# ExternalDisplay.net
KiCad netlist of a schematic drawn in Altium Designer
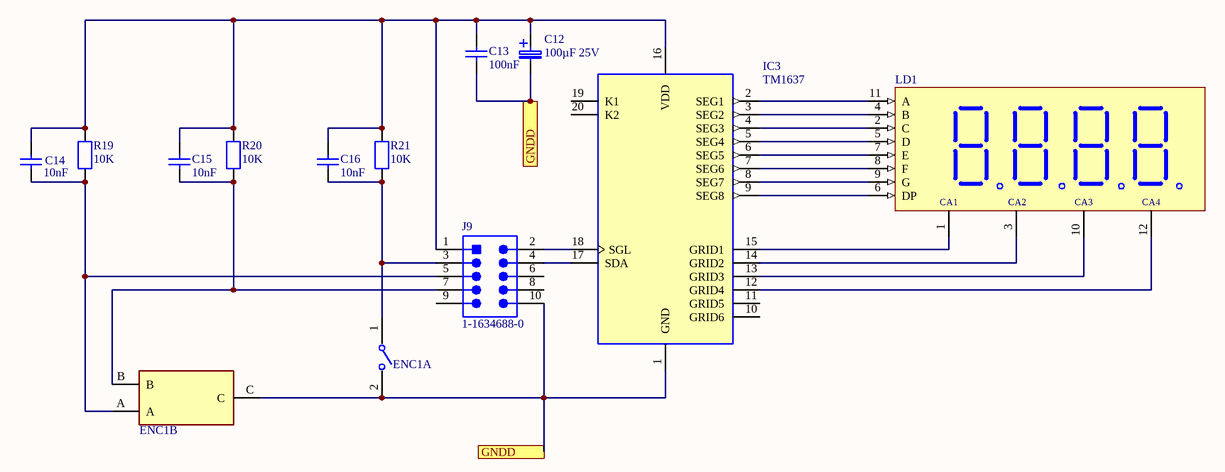
[diagram p0: ExternalDisplay.SchDoc]

(export (version "E")
  (design (tool "Eeschema 10.0.6"))
  (components
    (comp (ref "C12")
      (value "100µF 25V")
      (footprint "TAP106M050BRW")
      (description "Tantalum Capacitors - Solid Leaded 50V 10uF 20% ESR=1.6 Ohm TAP106M050BRW")
      (fields
        (field (name "MOUSER PART NUMBER") "581-TAP106M050BRW")
        (field (name "MANUFACTURER_PART_NUMBER") "TAP106M050BRW")
      )
      (libsource (lib "SolderStation") (part "capacitor THT radial tantalum"))
    )
    (comp (ref "C13")
      (value "100nF")
      (footprint "CAPC2012X88N")
      (fields (field (name "MANUFACTURER") "Kemet") (field (name "PART NUMBER") "C0402C104K4RACTU"))
      (libsource (lib "SolderStation") (part "Capacitor ceramic 0805"))
    )
    (comp (ref "C14")
      (value "10nF")
      (footprint "CAPC2012X88N")
      (fields (field (name "MANUFACTURER") "Kemet") (field (name "PART NUMBER") "C0402C104K4RACTU"))
      (libsource (lib "SolderStation") (part "Capacitor ceramic 0805"))
    )
    (comp (ref "C15")
      (value "10nF")
      (footprint "CAPC2012X88N")
      (fields (field (name "MANUFACTURER") "Kemet") (field (name "PART NUMBER") "C0402C104K4RACTU"))
      (libsource (lib "SolderStation") (part "Capacitor ceramic 0805"))
    )
    (comp (ref "C16")
      (value "10nF")
      (footprint "CAPC2012X88N")
      (fields (field (name "MANUFACTURER") "Kemet") (field (name "PART NUMBER") "C0402C104K4RACTU"))
      (libsource (lib "SolderStation") (part "Capacitor ceramic 0805"))
    )
    (comp (ref "ENC1")
      (value "PEC11R-4220F-S0012")
      (footprint "PEC11R_4220F_S0012")
      (description "ROTARY ENCODER MECHANICAL 12PPR")
      (libsource (lib "") (part "PEC11R-4220F-S0012_1"))
    )
    (comp (ref "IC3")
      (value "TM1637")
      (footprint "N-20")
      (description "LED Drive Control Special Circuit")
      (fields (field (name "MF") "Titan Micro Electronics"))
      (libsource (lib "SolderStation") (part "TM1637"))
    )
    (comp (ref "J9")
      (value "1-1634688-0")
      (footprint "TECO-1-1634688-0-10_V")
      (fields (field (name "MANUFACTURER") "TE Connectivity"))
      (libsource (lib "SolderStation") (part "pin header 2X5 10pins"))
    )
    (comp (ref "LD1")
      (value "KW4-801AVB")
      (footprint "KW4-801AVB/KW4-801CVB")
      (description "4-Digit LED Display TME")
      (libsource (lib "SolderStation") (part "KW4-801AVB"))
    )
    (comp (ref "R19")
      (value "10K")
      (footprint "RESC2012X50N")
      (fields (field (name "MANUFACTURER") "Vishay Dale") (field (name "PART NUMBER") "CRCW08050000Z0EA"))
      (libsource (lib "SolderStation") (part "resistor 0805"))
    )
    (comp (ref "R20")
      (value "10K")
      (footprint "RESC2012X50N")
      (fields (field (name "MANUFACTURER") "Vishay Dale") (field (name "PART NUMBER") "CRCW08050000Z0EA"))
      (libsource (lib "SolderStation") (part "resistor 0805"))
    )
    (comp (ref "R21")
      (value "10K")
      (footprint "RESC2012X50N")
      (fields (field (name "MANUFACTURER") "Vishay Dale") (field (name "PART NUMBER") "CRCW08050000Z0EA"))
      (libsource (lib "SolderStation") (part "resistor 0805"))
    )
  )
  (nets
    (net (code "1") (name "/GNDD") (class "Default")
      (node (ref "C12") (pin "2") (pinfunction "2_2") (pintype "passive"))
      (node (ref "C13") (pin "1") (pinfunction "1_1") (pintype "passive"))
      (node (ref "ENC1") (pin "2") (pinfunction "2_2") (pintype "passive"))
      (node (ref "ENC1") (pin "C") (pinfunction "C_C") (pintype "passive"))
      (node (ref "IC3") (pin "1") (pinfunction "GND_1") (pintype "power_in"))
      (node (ref "J9") (pin "10") (pinfunction "10_10") (pintype "passive"))
    )
    (net (code "2") (name "Net-(C14-Pad1)") (class "Default")
      (node (ref "C14") (pin "1") (pinfunction "1_1") (pintype "passive"))
      (node (ref "ENC1") (pin "A") (pinfunction "A_A") (pintype "passive"))
      (node (ref "J9") (pin "5") (pinfunction "5_5") (pintype "passive"))
      (node (ref "R19") (pin "1") (pinfunction "1_1") (pintype "passive"))
    )
    (net (code "3") (name "Net-(C15-Pad1)") (class "Default")
      (node (ref "C15") (pin "1") (pinfunction "1_1") (pintype "passive"))
      (node (ref "ENC1") (pin "B") (pinfunction "B_B") (pintype "passive"))
      (node (ref "J9") (pin "7") (pinfunction "7_7") (pintype "passive"))
      (node (ref "R20") (pin "1") (pinfunction "1_1") (pintype "passive"))
    )
    (net (code "4") (name "Net-(C16-Pad1)") (class "Default")
      (node (ref "C16") (pin "1") (pinfunction "1_1") (pintype "passive"))
      (node (ref "ENC1") (pin "1") (pinfunction "1_1") (pintype "passive"))
      (node (ref "J9") (pin "3") (pinfunction "3_3") (pintype "passive"))
      (node (ref "R21") (pin "1") (pinfunction "1_1") (pintype "passive"))
    )
    (net (code "5") (name "Net-(IC3-GRID1)") (class "Default")
      (node (ref "IC3") (pin "15") (pinfunction "GRID1_15") (pintype "passive"))
      (node (ref "LD1") (pin "1") (pinfunction "CA1_1") (pintype "passive"))
    )
    (net (code "6") (name "Net-(IC3-GRID2)") (class "Default")
      (node (ref "IC3") (pin "14") (pinfunction "GRID2_14") (pintype "passive"))
      (node (ref "LD1") (pin "3") (pinfunction "13_3") (pintype "passive"))
    )
    (net (code "7") (name "Net-(IC3-GRID3)") (class "Default")
      (node (ref "IC3") (pin "13") (pinfunction "GRID3_13") (pintype "passive"))
      (node (ref "LD1") (pin "10") (pinfunction "14_10") (pintype "passive"))
    )
    (net (code "8") (name "Net-(IC3-GRID4)") (class "Default")
      (node (ref "IC3") (pin "12") (pinfunction "GRID4_12") (pintype "passive"))
      (node (ref "LD1") (pin "12") (pinfunction "15_12") (pintype "passive"))
    )
    (net (code "9") (name "Net-(IC3-SDA)") (class "Default")
      (node (ref "IC3") (pin "17") (pinfunction "SDA_17") (pintype "passive"))
      (node (ref "J9") (pin "4") (pinfunction "4_4") (pintype "passive"))
    )
    (net (code "10") (name "Net-(IC3-SEG1)") (class "Default")
      (node (ref "IC3") (pin "2") (pinfunction "SEG1_2") (pintype "output"))
      (node (ref "LD1") (pin "11") (pinfunction "A_11") (pintype "input"))
    )
    (net (code "11") (name "Net-(IC3-SEG2)") (class "Default")
      (node (ref "IC3") (pin "3") (pinfunction "SEG2_3") (pintype "output"))
      (node (ref "LD1") (pin "4") (pinfunction "B_4") (pintype "input"))
    )
    (net (code "12") (name "Net-(IC3-SEG3)") (class "Default")
      (node (ref "IC3") (pin "4") (pinfunction "SEG3_4") (pintype "output"))
      (node (ref "LD1") (pin "2") (pinfunction "C_2") (pintype "input"))
    )
    (net (code "13") (name "Net-(IC3-SEG4)") (class "Default")
      (node (ref "IC3") (pin "5") (pinfunction "SEG4_5") (pintype "output"))
      (node (ref "LD1") (pin "5") (pinfunction "D_5") (pintype "input"))
    )
    (net (code "14") (name "Net-(IC3-SEG5)") (class "Default")
      (node (ref "IC3") (pin "6") (pinfunction "SEG5_6") (pintype "output"))
      (node (ref "LD1") (pin "7") (pinfunction "E_7") (pintype "input"))
    )
    (net (code "15") (name "Net-(IC3-SEG6)") (class "Default")
      (node (ref "IC3") (pin "7") (pinfunction "SEG6_7") (pintype "output"))
      (node (ref "LD1") (pin "8") (pinfunction "F_8") (pintype "input"))
    )
    (net (code "16") (name "Net-(IC3-SEG7)") (class "Default")
      (node (ref "IC3") (pin "8") (pinfunction "SEG7_8") (pintype "output"))
      (node (ref "LD1") (pin "9") (pinfunction "G_9") (pintype "input"))
    )
    (net (code "17") (name "Net-(IC3-SEG8)") (class "Default")
      (node (ref "IC3") (pin "9") (pinfunction "SEG8_9") (pintype "output"))
      (node (ref "LD1") (pin "6") (pinfunction "DP_6") (pintype "input"))
    )
    (net (code "18") (name "Net-(IC3-SGL)") (class "Default")
      (node (ref "IC3") (pin "18") (pinfunction "SGL_18") (pintype "passive"))
      (node (ref "J9") (pin "2") (pinfunction "2_2") (pintype "passive"))
    )
    (net (code "19") (name "Net-(IC3-VDD)") (class "Default")
      (node (ref "C12") (pin "1") (pinfunction "1_1") (pintype "passive"))
      (node (ref "C13") (pin "2") (pinfunction "2_2") (pintype "passive"))
      (node (ref "C14") (pin "2") (pinfunction "2_2") (pintype "passive"))
      (node (ref "C15") (pin "2") (pinfunction "2_2") (pintype "passive"))
      (node (ref "C16") (pin "2") (pinfunction "2_2") (pintype "passive"))
      (node (ref "IC3") (pin "16") (pinfunction "VDD_16") (pintype "power_in"))
      (node (ref "J9") (pin "1") (pinfunction "1_1") (pintype "passive"))
      (node (ref "R19") (pin "2") (pinfunction "2_2") (pintype "passive"))
      (node (ref "R20") (pin "2") (pinfunction "2_2") (pintype "passive"))
      (node (ref "R21") (pin "2") (pinfunction "2_2") (pintype "passive"))
    )
    (net (code "20") (name "unconnected-(IC3-GRID5-Pad11)") (class "Default")
      (node (ref "IC3") (pin "11") (pinfunction "GRID5_11") (pintype "passive"))
    )
    (net (code "21") (name "unconnected-(IC3-GRID6-Pad10)") (class "Default")
      (node (ref "IC3") (pin "10") (pinfunction "GRID6_10") (pintype "passive"))
    )
    (net (code "22") (name "unconnected-(IC3-K1-Pad19)") (class "Default")
      (node (ref "IC3") (pin "19") (pinfunction "K1_19") (pintype "passive"))
    )
    (net (code "23") (name "unconnected-(IC3-K2-Pad20)") (class "Default")
      (node (ref "IC3") (pin "20") (pinfunction "K2_20") (pintype "passive"))
    )
    (net (code "24") (name "unconnected-(J9-Pad6)") (class "Default")
      (node (ref "J9") (pin "6") (pinfunction "6_6") (pintype "passive"))
    )
    (net (code "25") (name "unconnected-(J9-Pad8)") (class "Default")
      (node (ref "J9") (pin "8") (pinfunction "8_8") (pintype "passive"))
    )
    (net (code "26") (name "unconnected-(J9-Pad9)") (class "Default")
      (node (ref "J9") (pin "9") (pinfunction "9_9") (pintype "passive"))
    )
  )
)
